# WiFiCPU.net
KiCad netlist of a schematic drawn in EAGLE
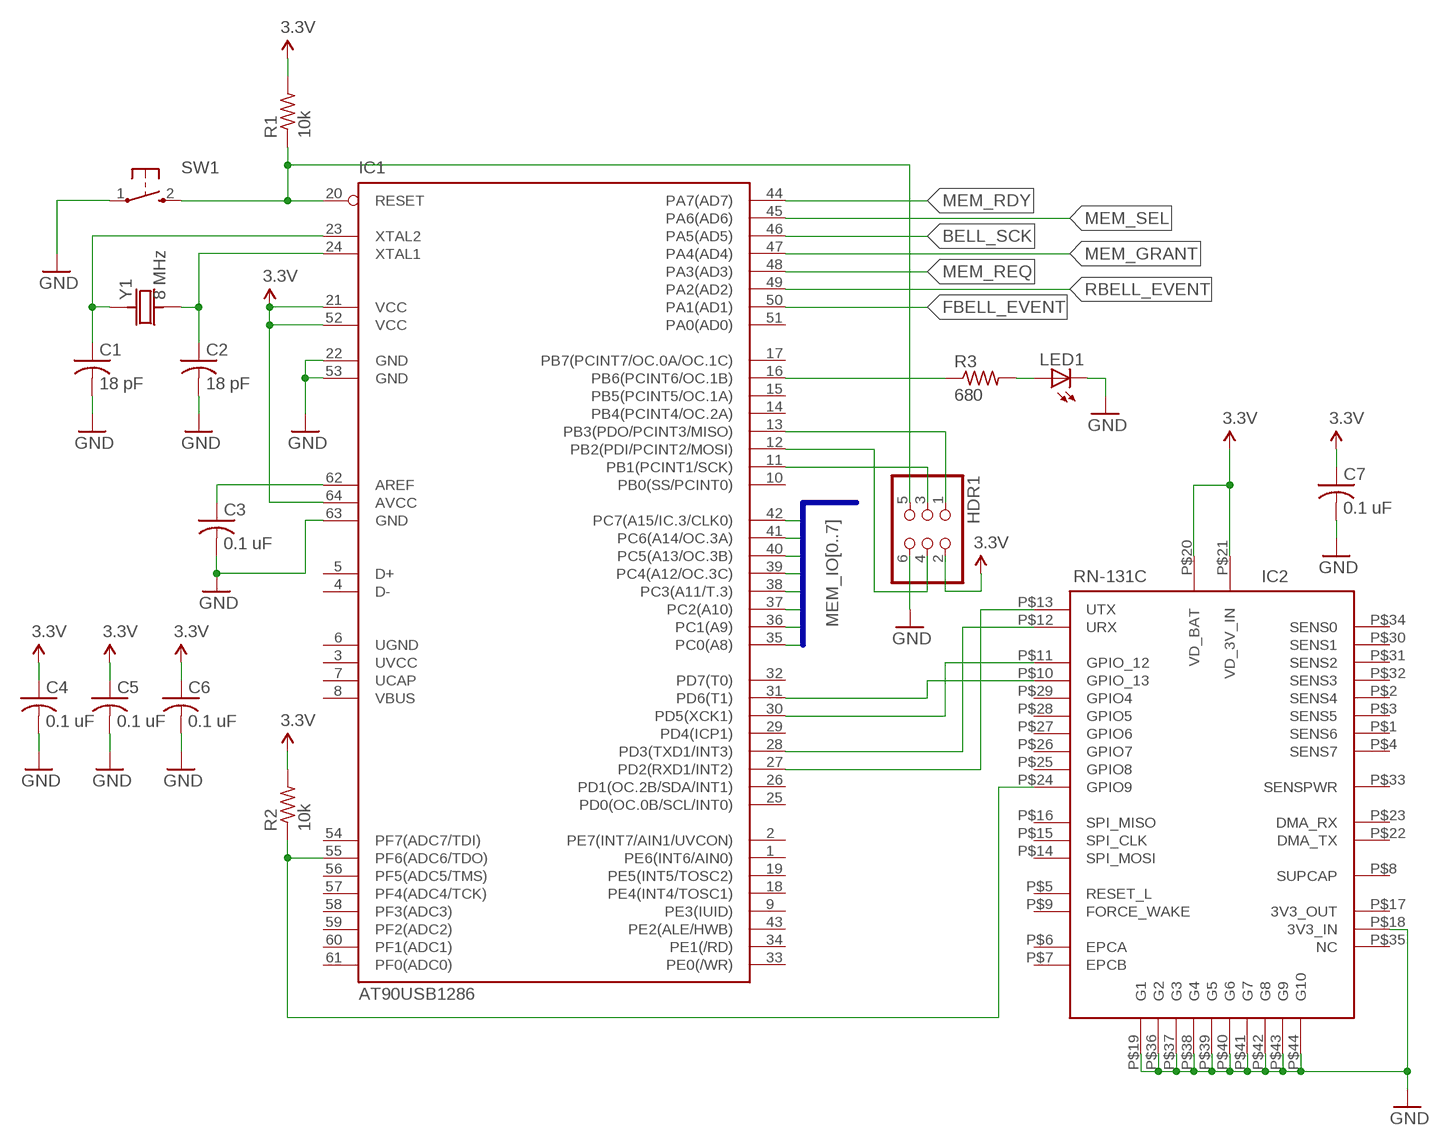
[diagram p0: schematic, sheet 1]

(export (version "E")
  (design (tool "Eeschema 10.0.6"))
  (components
    (comp (ref "C1")
      (value "18 pF")
      (footprint "eagle-import:0603_CAP")
      (libsource (lib "eagle-import") (part "CAP0603"))
    )
    (comp (ref "C2")
      (value "18 pF")
      (footprint "eagle-import:0603_CAP")
      (libsource (lib "eagle-import") (part "CAP0603"))
    )
    (comp (ref "C3")
      (value "0.1 uF")
      (footprint "eagle-import:0603_CAP")
      (libsource (lib "eagle-import") (part "CAP0603"))
    )
    (comp (ref "C4")
      (value "0.1 uF")
      (footprint "eagle-import:0603_CAP")
      (libsource (lib "eagle-import") (part "CAP0603"))
    )
    (comp (ref "C5")
      (value "0.1 uF")
      (footprint "eagle-import:0603_CAP")
      (libsource (lib "eagle-import") (part "CAP0603"))
    )
    (comp (ref "C6")
      (value "0.1 uF")
      (footprint "eagle-import:0603_CAP")
      (libsource (lib "eagle-import") (part "CAP0603"))
    )
    (comp (ref "C7")
      (value "0.1 uF")
      (footprint "eagle-import:0603_CAP")
      (libsource (lib "eagle-import") (part "CAP0603"))
    )
    (comp (ref "HDR1")
      (value "HEADER_2X3")
      (footprint "eagle-import:HEADER_2X3")
      (fields (field (name "MANF") "FCI"))
      (libsource (lib "eagle-import") (part "HEADER_2X3"))
    )
    (comp (ref "IC1")
      (value "AT90USB1286")
      (footprint "eagle-import:TQFP64")
      (fields (field (name "MANF") "Atmel") (field (name "DIGIKEY#") "AT90USB1286-AURCT-ND"))
      (libsource (lib "eagle-import") (part "AT90USB1286"))
    )
    (comp (ref "IC2")
      (value "RN-131C")
      (footprint "eagle-import:RN-131G")
      (fields (field (name "MANF") "Microchip Technology"))
      (libsource (lib "eagle-import") (part "RN-131C"))
    )
    (comp (ref "LED1")
      (value "LED0603")
      (footprint "eagle-import:0603_LED")
      (fields (field (name "MANF") "Avago Technologies"))
      (libsource (lib "eagle-import") (part "LED0603"))
    )
    (comp (ref "R1")
      (value "10k")
      (footprint "eagle-import:0603_RESISTOR")
      (libsource (lib "eagle-import") (part "RESISTOR0603"))
    )
    (comp (ref "R2")
      (value "10k")
      (footprint "eagle-import:0603_RESISTOR")
      (libsource (lib "eagle-import") (part "RESISTOR0603"))
    )
    (comp (ref "R3")
      (value "680")
      (footprint "eagle-import:0603_RESISTOR")
      (libsource (lib "eagle-import") (part "RESISTOR0603"))
    )
    (comp (ref "SW1")
      (value "SWITCH")
      (footprint "eagle-import:SWITCH_TAC")
      (fields (field (name "MANF") "E-Switch"))
      (libsource (lib "eagle-import") (part "SWITCH"))
    )
    (comp (ref "Y1")
      (value "8 MHz")
      (footprint "eagle-import:CRYSTAL_5X3")
      (libsource (lib "eagle-import") (part "CRYSTAL5X3"))
    )
  )
  (nets
    (net (code "10") (name "/UCAP") (class "Default")
      (node (ref "IC1") (pin "7") (pinfunction "UCAP_7") (pintype "power_in"))
    )
    (net (code "11") (name "/UGND") (class "Default")
      (node (ref "IC1") (pin "6") (pinfunction "UGND_6") (pintype "power_in"))
    )
    (net (code "12") (name "/UVCC") (class "Default")
      (node (ref "IC1") (pin "3") (pinfunction "UVCC_3") (pintype "power_in"))
    )
    (net (code "13") (name "/VBUS") (class "Default")
      (node (ref "IC1") (pin "8") (pinfunction "VBUS_8") (pintype "power_in"))
    )
    (net (code "14") (name "3.3V") (class "Default")
      (node (ref "C4") (pin "1") (pinfunction "1_1") (pintype "passive"))
      (node (ref "C5") (pin "1") (pinfunction "1_1") (pintype "passive"))
      (node (ref "C6") (pin "1") (pinfunction "1_1") (pintype "passive"))
      (node (ref "C7") (pin "1") (pinfunction "1_1") (pintype "passive"))
      (node (ref "HDR1") (pin "2") (pinfunction "2_2") (pintype "passive"))
      (node (ref "IC1") (pin "21") (pinfunction "VCC_21") (pintype "power_in"))
      (node (ref "IC1") (pin "52") (pinfunction "VCC_52") (pintype "power_in"))
      (node (ref "IC1") (pin "64") (pinfunction "AVCC_64") (pintype "bidirectional"))
      (node (ref "IC2") (pin "P$20") (pinfunction "VD_BAT_P$20") (pintype "bidirectional"))
      (node (ref "IC2") (pin "P$21") (pinfunction "VD_3V_IN_P$21") (pintype "bidirectional"))
      (node (ref "R1") (pin "2") (pinfunction "2_2") (pintype "passive"))
      (node (ref "R2") (pin "2") (pinfunction "2_2") (pintype "passive"))
    )
    (net (code "15") (name "BELL_SCK") (class "Default")
      (node (ref "IC1") (pin "46") (pinfunction "PA5(AD5)_46") (pintype "bidirectional"))
    )
    (net (code "16") (name "FBELL_EVENT") (class "Default")
      (node (ref "IC1") (pin "50") (pinfunction "PA1(AD1)_50") (pintype "bidirectional"))
    )
    (net (code "17") (name "GND") (class "Default")
      (node (ref "C1") (pin "2") (pinfunction "2_2") (pintype "passive"))
      (node (ref "C2") (pin "2") (pinfunction "2_2") (pintype "passive"))
      (node (ref "C3") (pin "2") (pinfunction "2_2") (pintype "passive"))
      (node (ref "C4") (pin "2") (pinfunction "2_2") (pintype "passive"))
      (node (ref "C5") (pin "2") (pinfunction "2_2") (pintype "passive"))
      (node (ref "C6") (pin "2") (pinfunction "2_2") (pintype "passive"))
      (node (ref "C7") (pin "2") (pinfunction "2_2") (pintype "passive"))
      (node (ref "HDR1") (pin "6") (pinfunction "6_6") (pintype "passive"))
      (node (ref "IC1") (pin "22") (pinfunction "GND_22") (pintype "power_in"))
      (node (ref "IC1") (pin "53") (pinfunction "GND_53") (pintype "power_in"))
      (node (ref "IC1") (pin "63") (pinfunction "GND_63") (pintype "power_in"))
      (node (ref "IC2") (pin "P$18") (pinfunction "3V3_IN_P$18") (pintype "bidirectional"))
      (node (ref "IC2") (pin "P$19") (pinfunction "G1_P$19") (pintype "bidirectional"))
      (node (ref "IC2") (pin "P$36") (pinfunction "G2_P$36") (pintype "bidirectional"))
      (node (ref "IC2") (pin "P$37") (pinfunction "G3_P$37") (pintype "bidirectional"))
      (node (ref "IC2") (pin "P$38") (pinfunction "G4_P$38") (pintype "bidirectional"))
      (node (ref "IC2") (pin "P$39") (pinfunction "G5_P$39") (pintype "bidirectional"))
      (node (ref "IC2") (pin "P$40") (pinfunction "G6_P$40") (pintype "bidirectional"))
      (node (ref "IC2") (pin "P$41") (pinfunction "G7_P$41") (pintype "bidirectional"))
      (node (ref "IC2") (pin "P$42") (pinfunction "G8_P$42") (pintype "bidirectional"))
      (node (ref "IC2") (pin "P$43") (pinfunction "G9_P$43") (pintype "bidirectional"))
      (node (ref "IC2") (pin "P$44") (pinfunction "G10_P$44") (pintype "bidirectional"))
      (node (ref "LED1") (pin "C") (pinfunction "C_C") (pintype "passive"))
      (node (ref "SW1") (pin "1") (pinfunction "1_1") (pintype "passive"))
    )
    (net (code "18") (name "MEM_GRANT") (class "Default")
      (node (ref "IC1") (pin "47") (pinfunction "PA4(AD4)_47") (pintype "bidirectional"))
    )
    (net (code "19") (name "MEM_RDY") (class "Default")
      (node (ref "IC1") (pin "44") (pinfunction "PA7(AD7)_44") (pintype "bidirectional"))
    )
    (net (code "20") (name "MEM_REQ") (class "Default")
      (node (ref "IC1") (pin "48") (pinfunction "PA3(AD3)_48") (pintype "bidirectional"))
    )
    (net (code "21") (name "MEM_SEL") (class "Default")
      (node (ref "IC1") (pin "45") (pinfunction "PA6(AD6)_45") (pintype "bidirectional"))
    )
    (net (code "22") (name "Net-(IC1-AREF)") (class "Default")
      (node (ref "C3") (pin "1") (pinfunction "1_1") (pintype "passive"))
      (node (ref "IC1") (pin "62") (pinfunction "AREF_62") (pintype "bidirectional"))
    )
    (net (code "23") (name "Net-(IC1-PB1(PCINT1{slash}SCK))") (class "Default")
      (node (ref "HDR1") (pin "3") (pinfunction "3_3") (pintype "passive"))
      (node (ref "IC1") (pin "11") (pinfunction "PB1(PCINT1/SCK)_11") (pintype "bidirectional"))
    )
    (net (code "24") (name "Net-(IC1-PB2(PDI{slash}PCINT2{slash}MOSI))") (class "Default")
      (node (ref "HDR1") (pin "4") (pinfunction "4_4") (pintype "passive"))
      (node (ref "IC1") (pin "12") (pinfunction "PB2(PDI/PCINT2/MOSI)_12") (pintype "bidirectional"))
    )
    (net (code "25") (name "Net-(IC1-PB3(PDO{slash}PCINT3{slash}MISO))") (class "Default")
      (node (ref "HDR1") (pin "1") (pinfunction "1_1") (pintype "passive"))
      (node (ref "IC1") (pin "13") (pinfunction "PB3(PDO/PCINT3/MISO)_13") (pintype "bidirectional"))
    )
    (net (code "26") (name "Net-(IC1-PB6(PCINT6{slash}OC.1B))") (class "Default")
      (node (ref "IC1") (pin "16") (pinfunction "PB6(PCINT6/OC.1B)_16") (pintype "bidirectional"))
      (node (ref "R3") (pin "1") (pinfunction "1_1") (pintype "passive"))
    )
    (net (code "27") (name "Net-(IC1-PD2(RXD1{slash}INT2))") (class "Default")
      (node (ref "IC1") (pin "27") (pinfunction "PD2(RXD1/INT2)_27") (pintype "bidirectional"))
      (node (ref "IC2") (pin "P$13") (pinfunction "UTX_P$13") (pintype "bidirectional"))
    )
    (net (code "28") (name "Net-(IC1-PD3(TXD1{slash}INT3))") (class "Default")
      (node (ref "IC1") (pin "28") (pinfunction "PD3(TXD1/INT3)_28") (pintype "bidirectional"))
      (node (ref "IC2") (pin "P$12") (pinfunction "URX_P$12") (pintype "bidirectional"))
    )
    (net (code "29") (name "Net-(IC1-PD5(XCK1))") (class "Default")
      (node (ref "IC1") (pin "30") (pinfunction "PD5(XCK1)_30") (pintype "bidirectional"))
      (node (ref "IC2") (pin "P$11") (pinfunction "GPIO_12_P$11") (pintype "bidirectional"))
    )
    (net (code "30") (name "Net-(IC1-PD6(T1))") (class "Default")
      (node (ref "IC1") (pin "31") (pinfunction "PD6(T1)_31") (pintype "bidirectional"))
      (node (ref "IC2") (pin "P$10") (pinfunction "GPIO_13_P$10") (pintype "bidirectional"))
    )
    (net (code "31") (name "Net-(IC1-PF6(ADC6{slash}TDO))") (class "Default")
      (node (ref "IC1") (pin "55") (pinfunction "PF6(ADC6/TDO)_55") (pintype "bidirectional"))
      (node (ref "IC2") (pin "P$24") (pinfunction "GPIO9_P$24") (pintype "bidirectional"))
      (node (ref "R2") (pin "1") (pinfunction "1_1") (pintype "passive"))
    )
    (net (code "32") (name "Net-(IC1-RESET)") (class "Default")
      (node (ref "HDR1") (pin "5") (pinfunction "5_5") (pintype "passive"))
      (node (ref "IC1") (pin "20") (pinfunction "RESET_20") (pintype "input"))
      (node (ref "R1") (pin "1") (pinfunction "1_1") (pintype "passive"))
      (node (ref "SW1") (pin "2") (pinfunction "2_2") (pintype "passive"))
    )
    (net (code "33") (name "Net-(IC1-XTAL1)") (class "Default")
      (node (ref "C2") (pin "1") (pinfunction "1_1") (pintype "passive"))
      (node (ref "IC1") (pin "24") (pinfunction "XTAL1_24") (pintype "bidirectional"))
      (node (ref "Y1") (pin "2") (pinfunction "2_2") (pintype "passive"))
    )
    (net (code "34") (name "Net-(IC1-XTAL2)") (class "Default")
      (node (ref "C1") (pin "1") (pinfunction "1_1") (pintype "passive"))
      (node (ref "IC1") (pin "23") (pinfunction "XTAL2_23") (pintype "bidirectional"))
      (node (ref "Y1") (pin "1") (pinfunction "1_1") (pintype "passive"))
    )
    (net (code "35") (name "Net-(LED1-PadA)") (class "Default")
      (node (ref "LED1") (pin "A") (pinfunction "A_A") (pintype "passive"))
      (node (ref "R3") (pin "2") (pinfunction "2_2") (pintype "passive"))
    )
    (net (code "36") (name "RBELL_EVENT") (class "Default")
      (node (ref "IC1") (pin "49") (pinfunction "PA2(AD2)_49") (pintype "bidirectional"))
    )
    (net (code "37") (name "unconnected-(IC1-D+-Pad5)") (class "Default")
      (node (ref "IC1") (pin "5") (pinfunction "D+_5") (pintype "bidirectional"))
    )
    (net (code "38") (name "unconnected-(IC1-D--Pad4)") (class "Default")
      (node (ref "IC1") (pin "4") (pinfunction "D-_4") (pintype "bidirectional"))
    )
    (net (code "39") (name "unconnected-(IC1-PA0(AD0)-Pad51)") (class "Default")
      (node (ref "IC1") (pin "51") (pinfunction "PA0(AD0)_51") (pintype "bidirectional"))
    )
    (net (code "40") (name "unconnected-(IC1-PB0(SS{slash}PCINT0)-Pad10)") (class "Default")
      (node (ref "IC1") (pin "10") (pinfunction "PB0(SS/PCINT0)_10") (pintype "bidirectional"))
    )
    (net (code "41") (name "unconnected-(IC1-PB4(PCINT4{slash}OC.2A)-Pad14)") (class "Default")
      (node (ref "IC1") (pin "14") (pinfunction "PB4(PCINT4/OC.2A)_14") (pintype "bidirectional"))
    )
    (net (code "42") (name "unconnected-(IC1-PB5(PCINT5{slash}OC.1A)-Pad15)") (class "Default")
      (node (ref "IC1") (pin "15") (pinfunction "PB5(PCINT5/OC.1A)_15") (pintype "bidirectional"))
    )
    (net (code "43") (name "unconnected-(IC1-PB7(PCINT7{slash}OC.0A{slash}OC.1C)-Pad17)") (class "Default")
      (node (ref "IC1") (pin "17") (pinfunction "PB7(PCINT7/OC.0A/OC.1C)_17") (pintype "bidirectional"))
    )
    (net (code "44") (name "unconnected-(IC1-PC0(A8)-Pad35)") (class "Default")
      (node (ref "IC1") (pin "35") (pinfunction "PC0(A8)_35") (pintype "bidirectional"))
    )
    (net (code "45") (name "unconnected-(IC1-PC1(A9)-Pad36)") (class "Default")
      (node (ref "IC1") (pin "36") (pinfunction "PC1(A9)_36") (pintype "bidirectional"))
    )
    (net (code "46") (name "unconnected-(IC1-PC2(A10)-Pad37)") (class "Default")
      (node (ref "IC1") (pin "37") (pinfunction "PC2(A10)_37") (pintype "bidirectional"))
    )
    (net (code "47") (name "unconnected-(IC1-PC3(A11{slash}T.3)-Pad38)") (class "Default")
      (node (ref "IC1") (pin "38") (pinfunction "PC3(A11/T.3)_38") (pintype "bidirectional"))
    )
    (net (code "48") (name "unconnected-(IC1-PC4(A12{slash}OC.3C)-Pad39)") (class "Default")
      (node (ref "IC1") (pin "39") (pinfunction "PC4(A12/OC.3C)_39") (pintype "bidirectional"))
    )
    (net (code "49") (name "unconnected-(IC1-PC5(A13{slash}OC.3B)-Pad40)") (class "Default")
      (node (ref "IC1") (pin "40") (pinfunction "PC5(A13/OC.3B)_40") (pintype "bidirectional"))
    )
    (net (code "50") (name "unconnected-(IC1-PC6(A14{slash}OC.3A)-Pad41)") (class "Default")
      (node (ref "IC1") (pin "41") (pinfunction "PC6(A14/OC.3A)_41") (pintype "bidirectional"))
    )
    (net (code "51") (name "unconnected-(IC1-PC7(A15{slash}IC.3{slash}CLK0)-Pad42)") (class "Default")
      (node (ref "IC1") (pin "42") (pinfunction "PC7(A15/IC.3/CLK0)_42") (pintype "bidirectional"))
    )
    (net (code "52") (name "unconnected-(IC1-PD0(OC.0B{slash}SCL{slash}INT0)-Pad25)") (class "Default")
      (node (ref "IC1") (pin "25") (pinfunction "PD0(OC.0B/SCL/INT0)_25") (pintype "bidirectional"))
    )
    (net (code "53") (name "unconnected-(IC1-PD1(OC.2B{slash}SDA{slash}INT1)-Pad26)") (class "Default")
      (node (ref "IC1") (pin "26") (pinfunction "PD1(OC.2B/SDA/INT1)_26") (pintype "bidirectional"))
    )
    (net (code "54") (name "unconnected-(IC1-PD4(ICP1)-Pad29)") (class "Default")
      (node (ref "IC1") (pin "29") (pinfunction "PD4(ICP1)_29") (pintype "bidirectional"))
    )
    (net (code "55") (name "unconnected-(IC1-PD7(T0)-Pad32)") (class "Default")
      (node (ref "IC1") (pin "32") (pinfunction "PD7(T0)_32") (pintype "bidirectional"))
    )
    (net (code "56") (name "unconnected-(IC1-PE0({slash}WR)-Pad33)") (class "Default")
      (node (ref "IC1") (pin "33") (pinfunction "PE0(/WR)_33") (pintype "bidirectional"))
    )
    (net (code "57") (name "unconnected-(IC1-PE1({slash}RD)-Pad34)") (class "Default")
      (node (ref "IC1") (pin "34") (pinfunction "PE1(/RD)_34") (pintype "bidirectional"))
    )
    (net (code "58") (name "unconnected-(IC1-PE2(ALE{slash}HWB)-Pad43)") (class "Default")
      (node (ref "IC1") (pin "43") (pinfunction "PE2(ALE/HWB)_43") (pintype "bidirectional"))
    )
    (net (code "59") (name "unconnected-(IC1-PE3(IUID)-Pad9)") (class "Default")
      (node (ref "IC1") (pin "9") (pinfunction "PE3(IUID)_9") (pintype "bidirectional"))
    )
    (net (code "60") (name "unconnected-(IC1-PE4(INT4{slash}TOSC1)-Pad18)") (class "Default")
      (node (ref "IC1") (pin "18") (pinfunction "PE4(INT4/TOSC1)_18") (pintype "bidirectional"))
    )
    (net (code "61") (name "unconnected-(IC1-PE5(INT5{slash}TOSC2)-Pad19)") (class "Default")
      (node (ref "IC1") (pin "19") (pinfunction "PE5(INT5/TOSC2)_19") (pintype "bidirectional"))
    )
    (net (code "62") (name "unconnected-(IC1-PE6(INT6{slash}AIN0)-Pad1)") (class "Default")
      (node (ref "IC1") (pin "1") (pinfunction "PE6(INT6/AIN0)_1") (pintype "bidirectional"))
    )
    (net (code "63") (name "unconnected-(IC1-PE7(INT7{slash}AIN1{slash}UVCON)-Pad2)") (class "Default")
      (node (ref "IC1") (pin "2") (pinfunction "PE7(INT7/AIN1/UVCON)_2") (pintype "bidirectional"))
    )
    (net (code "64") (name "unconnected-(IC1-PF0(ADC0)-Pad61)") (class "Default")
      (node (ref "IC1") (pin "61") (pinfunction "PF0(ADC0)_61") (pintype "bidirectional"))
    )
    (net (code "65") (name "unconnected-(IC1-PF1(ADC1)-Pad60)") (class "Default")
      (node (ref "IC1") (pin "60") (pinfunction "PF1(ADC1)_60") (pintype "bidirectional"))
    )
    (net (code "66") (name "unconnected-(IC1-PF2(ADC2)-Pad59)") (class "Default")
      (node (ref "IC1") (pin "59") (pinfunction "PF2(ADC2)_59") (pintype "bidirectional"))
    )
    (net (code "67") (name "unconnected-(IC1-PF3(ADC3)-Pad58)") (class "Default")
      (node (ref "IC1") (pin "58") (pinfunction "PF3(ADC3)_58") (pintype "bidirectional"))
    )
    (net (code "68") (name "unconnected-(IC1-PF4(ADC4{slash}TCK)-Pad57)") (class "Default")
      (node (ref "IC1") (pin "57") (pinfunction "PF4(ADC4/TCK)_57") (pintype "bidirectional"))
    )
    (net (code "69") (name "unconnected-(IC1-PF5(ADC5{slash}TMS)-Pad56)") (class "Default")
      (node (ref "IC1") (pin "56") (pinfunction "PF5(ADC5/TMS)_56") (pintype "bidirectional"))
    )
    (net (code "70") (name "unconnected-(IC1-PF7(ADC7{slash}TDI)-Pad54)") (class "Default")
      (node (ref "IC1") (pin "54") (pinfunction "PF7(ADC7/TDI)_54") (pintype "bidirectional"))
    )
    (net (code "71") (name "unconnected-(IC2-3V3_OUT-PadP$17)") (class "Default")
      (node (ref "IC2") (pin "P$17") (pinfunction "3V3_OUT_P$17") (pintype "bidirectional"))
    )
    (net (code "72") (name "unconnected-(IC2-DMA_RX-PadP$23)") (class "Default")
      (node (ref "IC2") (pin "P$23") (pinfunction "DMA_RX_P$23") (pintype "bidirectional"))
    )
    (net (code "73") (name "unconnected-(IC2-DMA_TX-PadP$22)") (class "Default")
      (node (ref "IC2") (pin "P$22") (pinfunction "DMA_TX_P$22") (pintype "bidirectional"))
    )
    (net (code "74") (name "unconnected-(IC2-EPCA-PadP$6)") (class "Default")
      (node (ref "IC2") (pin "P$6") (pinfunction "EPCA_P$6") (pintype "bidirectional"))
    )
    (net (code "75") (name "unconnected-(IC2-EPCB-PadP$7)") (class "Default")
      (node (ref "IC2") (pin "P$7") (pinfunction "EPCB_P$7") (pintype "bidirectional"))
    )
    (net (code "76") (name "unconnected-(IC2-FORCE_WAKE-PadP$9)") (class "Default")
      (node (ref "IC2") (pin "P$9") (pinfunction "FORCE_WAKE_P$9") (pintype "bidirectional"))
    )
    (net (code "77") (name "unconnected-(IC2-GPIO4-PadP$29)") (class "Default")
      (node (ref "IC2") (pin "P$29") (pinfunction "GPIO4_P$29") (pintype "bidirectional"))
    )
    (net (code "78") (name "unconnected-(IC2-GPIO5-PadP$28)") (class "Default")
      (node (ref "IC2") (pin "P$28") (pinfunction "GPIO5_P$28") (pintype "bidirectional"))
    )
    (net (code "79") (name "unconnected-(IC2-GPIO6-PadP$27)") (class "Default")
      (node (ref "IC2") (pin "P$27") (pinfunction "GPIO6_P$27") (pintype "bidirectional"))
    )
    (net (code "80") (name "unconnected-(IC2-GPIO7-PadP$26)") (class "Default")
      (node (ref "IC2") (pin "P$26") (pinfunction "GPIO7_P$26") (pintype "bidirectional"))
    )
    (net (code "81") (name "unconnected-(IC2-GPIO8-PadP$25)") (class "Default")
      (node (ref "IC2") (pin "P$25") (pinfunction "GPIO8_P$25") (pintype "bidirectional"))
    )
    (net (code "82") (name "unconnected-(IC2-NC-PadP$35)") (class "Default")
      (node (ref "IC2") (pin "P$35") (pinfunction "NC_P$35") (pintype "bidirectional"))
    )
    (net (code "83") (name "unconnected-(IC2-RESET_L-PadP$5)") (class "Default")
      (node (ref "IC2") (pin "P$5") (pinfunction "RESET_L_P$5") (pintype "bidirectional"))
    )
    (net (code "84") (name "unconnected-(IC2-SENS0-PadP$34)") (class "Default")
      (node (ref "IC2") (pin "P$34") (pinfunction "SENS0_P$34") (pintype "bidirectional"))
    )
    (net (code "85") (name "unconnected-(IC2-SENS1-PadP$30)") (class "Default")
      (node (ref "IC2") (pin "P$30") (pinfunction "SENS1_P$30") (pintype "bidirectional"))
    )
    (net (code "86") (name "unconnected-(IC2-SENS2-PadP$31)") (class "Default")
      (node (ref "IC2") (pin "P$31") (pinfunction "SENS2_P$31") (pintype "bidirectional"))
    )
    (net (code "87") (name "unconnected-(IC2-SENS3-PadP$32)") (class "Default")
      (node (ref "IC2") (pin "P$32") (pinfunction "SENS3_P$32") (pintype "bidirectional"))
    )
    (net (code "88") (name "unconnected-(IC2-SENS4-PadP$2)") (class "Default")
      (node (ref "IC2") (pin "P$2") (pinfunction "SENS4_P$2") (pintype "bidirectional"))
    )
    (net (code "89") (name "unconnected-(IC2-SENS5-PadP$3)") (class "Default")
      (node (ref "IC2") (pin "P$3") (pinfunction "SENS5_P$3") (pintype "bidirectional"))
    )
    (net (code "90") (name "unconnected-(IC2-SENS6-PadP$1)") (class "Default")
      (node (ref "IC2") (pin "P$1") (pinfunction "SENS6_P$1") (pintype "bidirectional"))
    )
    (net (code "91") (name "unconnected-(IC2-SENS7-PadP$4)") (class "Default")
      (node (ref "IC2") (pin "P$4") (pinfunction "SENS7_P$4") (pintype "bidirectional"))
    )
    (net (code "92") (name "unconnected-(IC2-SENSPWR-PadP$33)") (class "Default")
      (node (ref "IC2") (pin "P$33") (pinfunction "SENSPWR_P$33") (pintype "bidirectional"))
    )
    (net (code "93") (name "unconnected-(IC2-SPI_CLK-PadP$15)") (class "Default")
      (node (ref "IC2") (pin "P$15") (pinfunction "SPI_CLK_P$15") (pintype "bidirectional"))
    )
    (net (code "94") (name "unconnected-(IC2-SPI_MISO-PadP$16)") (class "Default")
      (node (ref "IC2") (pin "P$16") (pinfunction "SPI_MISO_P$16") (pintype "bidirectional"))
    )
    (net (code "95") (name "unconnected-(IC2-SPI_MOSI-PadP$14)") (class "Default")
      (node (ref "IC2") (pin "P$14") (pinfunction "SPI_MOSI_P$14") (pintype "bidirectional"))
    )
    (net (code "96") (name "unconnected-(IC2-SUPCAP-PadP$8)") (class "Default")
      (node (ref "IC2") (pin "P$8") (pinfunction "SUPCAP_P$8") (pintype "bidirectional"))
    )
  )
)
